# Consumer.net
KiCad netlist of a schematic drawn in Altium Designer
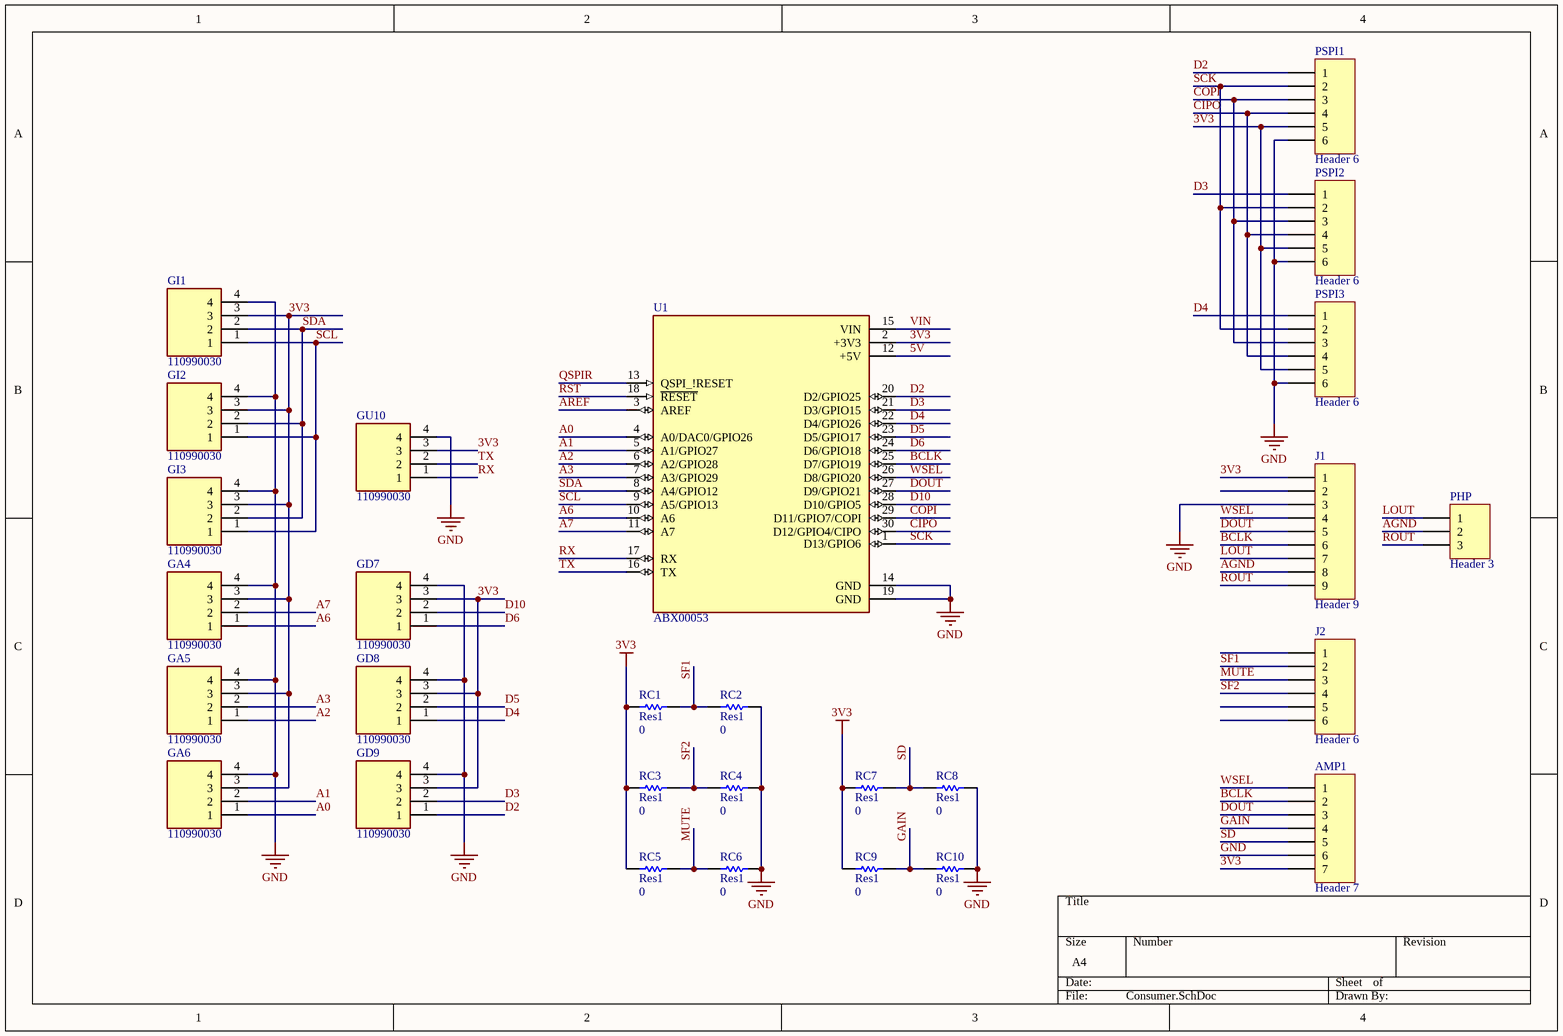
[diagram p0: Consumer.SchDoc]

(export (version "E")
  (design (tool "Eeschema 10.0.6"))
  (components
    (comp (ref "AMP1")
      (value "Header 7")
      (footprint "HDR1X7")
      (description "Header, 7-Pin")
      (fields (field (name "PUBLISHER") "Altium Limited"))
      (libsource (lib "Miscellaneous Connectors") (part "Header 7"))
    )
    (comp (ref "GA4")
      (value "110990030")
      (footprint "SEEED_110990030")
      (description "GROVE 2MM 4PIN VERT CONN 10PCS")
      (fields (field (name "MF") "Seeed Technology"))
      (libsource (lib "110990030") (part "110990030"))
    )
    (comp (ref "GA5")
      (value "110990030")
      (footprint "SEEED_110990030")
      (description "GROVE 2MM 4PIN VERT CONN 10PCS")
      (fields (field (name "MF") "Seeed Technology"))
      (libsource (lib "110990030") (part "110990030"))
    )
    (comp (ref "GA6")
      (value "110990030")
      (footprint "SEEED_110990030")
      (description "GROVE 2MM 4PIN VERT CONN 10PCS")
      (fields (field (name "MF") "Seeed Technology"))
      (libsource (lib "110990030") (part "110990030"))
    )
    (comp (ref "GD7")
      (value "110990030")
      (footprint "SEEED_110990030")
      (description "GROVE 2MM 4PIN VERT CONN 10PCS")
      (fields (field (name "MF") "Seeed Technology"))
      (libsource (lib "110990030") (part "110990030"))
    )
    (comp (ref "GD8")
      (value "110990030")
      (footprint "SEEED_110990030")
      (description "GROVE 2MM 4PIN VERT CONN 10PCS")
      (fields (field (name "MF") "Seeed Technology"))
      (libsource (lib "110990030") (part "110990030"))
    )
    (comp (ref "GD9")
      (value "110990030")
      (footprint "SEEED_110990030")
      (description "GROVE 2MM 4PIN VERT CONN 10PCS")
      (fields (field (name "MF") "Seeed Technology"))
      (libsource (lib "110990030") (part "110990030"))
    )
    (comp (ref "GI1")
      (value "110990030")
      (footprint "SEEED_110990030")
      (description "GROVE 2MM 4PIN VERT CONN 10PCS")
      (fields (field (name "MF") "Seeed Technology"))
      (libsource (lib "110990030") (part "110990030"))
    )
    (comp (ref "GI2")
      (value "110990030")
      (footprint "SEEED_110990030")
      (description "GROVE 2MM 4PIN VERT CONN 10PCS")
      (fields (field (name "MF") "Seeed Technology"))
      (libsource (lib "110990030") (part "110990030"))
    )
    (comp (ref "GI3")
      (value "110990030")
      (footprint "SEEED_110990030")
      (description "GROVE 2MM 4PIN VERT CONN 10PCS")
      (fields (field (name "MF") "Seeed Technology"))
      (libsource (lib "110990030") (part "110990030"))
    )
    (comp (ref "GU10")
      (value "110990030")
      (footprint "SEEED_110990030")
      (description "GROVE 2MM 4PIN VERT CONN 10PCS")
      (fields (field (name "MF") "Seeed Technology"))
      (libsource (lib "110990030") (part "110990030"))
    )
    (comp (ref "J1")
      (value "Header 9")
      (footprint "HDR1X9")
      (description "Header, 9-Pin")
      (fields (field (name "PUBLISHER") "Altium Limited"))
      (libsource (lib "Miscellaneous Connectors") (part "Header 9"))
    )
    (comp (ref "J2")
      (value "Header 6")
      (footprint "HDR1X6")
      (description "Header, 6-Pin")
      (fields (field (name "PUBLISHER") "Altium Limited"))
      (libsource (lib "Miscellaneous Connectors") (part "Header 6"))
    )
    (comp (ref "PHP")
      (value "Header 3")
      (footprint "HDR1X3")
      (description "Header, 3-Pin")
      (fields (field (name "PUBLISHER") "Altium Limited"))
      (libsource (lib "Miscellaneous Connectors") (part "Header 3"))
    )
    (comp (ref "PSPI1")
      (value "Header 6")
      (footprint "HDR1X6")
      (description "Header, 6-Pin")
      (fields (field (name "PUBLISHER") "Altium Limited"))
      (libsource (lib "Miscellaneous Connectors") (part "Header 6"))
    )
    (comp (ref "PSPI2")
      (value "Header 6")
      (footprint "HDR1X6")
      (description "Header, 6-Pin")
      (fields (field (name "PUBLISHER") "Altium Limited"))
      (libsource (lib "Miscellaneous Connectors") (part "Header 6"))
    )
    (comp (ref "PSPI3")
      (value "Header 6")
      (footprint "HDR1X6")
      (description "Header, 6-Pin")
      (fields (field (name "PUBLISHER") "Altium Limited"))
      (libsource (lib "Miscellaneous Connectors") (part "Header 6"))
    )
    (comp (ref "RC1")
      (value "Res1")
      (footprint "0603R-GENERIC")
      (description "Resistor")
      (fields (field (name "ALTIUM_VALUE") "0") (field (name "PUBLISHER") "Altium Limited"))
      (libsource (lib "Miscellaneous Devices") (part "Res1"))
    )
    (comp (ref "RC2")
      (value "Res1")
      (footprint "0603R-GENERIC")
      (description "Resistor")
      (fields (field (name "ALTIUM_VALUE") "0") (field (name "PUBLISHER") "Altium Limited"))
      (libsource (lib "Miscellaneous Devices") (part "Res1"))
    )
    (comp (ref "RC3")
      (value "Res1")
      (footprint "0603R-GENERIC")
      (description "Resistor")
      (fields (field (name "ALTIUM_VALUE") "0") (field (name "PUBLISHER") "Altium Limited"))
      (libsource (lib "Miscellaneous Devices") (part "Res1"))
    )
    (comp (ref "RC4")
      (value "Res1")
      (footprint "0603R-GENERIC")
      (description "Resistor")
      (fields (field (name "ALTIUM_VALUE") "0") (field (name "PUBLISHER") "Altium Limited"))
      (libsource (lib "Miscellaneous Devices") (part "Res1"))
    )
    (comp (ref "RC5")
      (value "Res1")
      (footprint "0603R-GENERIC")
      (description "Resistor")
      (fields (field (name "ALTIUM_VALUE") "0") (field (name "PUBLISHER") "Altium Limited"))
      (libsource (lib "Miscellaneous Devices") (part "Res1"))
    )
    (comp (ref "RC6")
      (value "Res1")
      (footprint "0603R-GENERIC")
      (description "Resistor")
      (fields (field (name "ALTIUM_VALUE") "0") (field (name "PUBLISHER") "Altium Limited"))
      (libsource (lib "Miscellaneous Devices") (part "Res1"))
    )
    (comp (ref "RC7")
      (value "Res1")
      (footprint "0603R-GENERIC")
      (description "Resistor")
      (fields (field (name "ALTIUM_VALUE") "0") (field (name "PUBLISHER") "Altium Limited"))
      (libsource (lib "Miscellaneous Devices") (part "Res1"))
    )
    (comp (ref "RC8")
      (value "Res1")
      (footprint "0603R-GENERIC")
      (description "Resistor")
      (fields (field (name "ALTIUM_VALUE") "0") (field (name "PUBLISHER") "Altium Limited"))
      (libsource (lib "Miscellaneous Devices") (part "Res1"))
    )
    (comp (ref "RC9")
      (value "Res1")
      (footprint "0603R-GENERIC")
      (description "Resistor")
      (fields (field (name "ALTIUM_VALUE") "0") (field (name "PUBLISHER") "Altium Limited"))
      (libsource (lib "Miscellaneous Devices") (part "Res1"))
    )
    (comp (ref "RC10")
      (value "Res1")
      (footprint "0603R-GENERIC")
      (description "Resistor")
      (fields (field (name "ALTIUM_VALUE") "0") (field (name "PUBLISHER") "Altium Limited"))
      (libsource (lib "Miscellaneous Devices") (part "Res1"))
    )
    (comp (ref "U1")
      (value "ABX00053")
      (footprint "MODULE_ABX00053")
      (description "ARDUINO NANO RP2040 CONNECT WITH")
      (fields (field (name "MF") "Arduino"))
      (libsource (lib "ABX00053") (part "ABX00053"))
    )
  )
  (nets
    (net (code "1") (name "/5V") (class "Default")
      (node (ref "U1") (pin "12") (pinfunction "+5V_12") (pintype "power_in"))
    )
    (net (code "2") (name "/A0") (class "Default")
      (node (ref "GA6") (pin "1") (pinfunction "1_1") (pintype "passive"))
      (node (ref "U1") (pin "4") (pinfunction "A0/DAC0/GPIO26_4") (pintype "bidirectional"))
    )
    (net (code "3") (name "/A1") (class "Default")
      (node (ref "GA6") (pin "2") (pinfunction "2_2") (pintype "passive"))
      (node (ref "U1") (pin "5") (pinfunction "A1/GPIO27_5") (pintype "bidirectional"))
    )
    (net (code "4") (name "/A2") (class "Default")
      (node (ref "GA5") (pin "1") (pinfunction "1_1") (pintype "passive"))
      (node (ref "U1") (pin "6") (pinfunction "A2/GPIO28_6") (pintype "bidirectional"))
    )
    (net (code "5") (name "/A3") (class "Default")
      (node (ref "GA5") (pin "2") (pinfunction "2_2") (pintype "passive"))
      (node (ref "U1") (pin "7") (pinfunction "A3/GPIO29_7") (pintype "bidirectional"))
    )
    (net (code "6") (name "/A6") (class "Default")
      (node (ref "GA4") (pin "1") (pinfunction "1_1") (pintype "passive"))
      (node (ref "U1") (pin "10") (pinfunction "A6_10") (pintype "bidirectional"))
    )
    (net (code "7") (name "/A7") (class "Default")
      (node (ref "GA4") (pin "2") (pinfunction "2_2") (pintype "passive"))
      (node (ref "U1") (pin "11") (pinfunction "A7_11") (pintype "bidirectional"))
    )
    (net (code "8") (name "/AGND") (class "Default")
      (node (ref "J1") (pin "8") (pinfunction "8_8") (pintype "passive"))
      (node (ref "PHP") (pin "2") (pinfunction "2_2") (pintype "passive"))
    )
    (net (code "9") (name "/AREF") (class "Default")
      (node (ref "U1") (pin "3") (pinfunction "AREF_3") (pintype "bidirectional"))
    )
    (net (code "10") (name "/BCLK") (class "Default")
      (node (ref "AMP1") (pin "2") (pinfunction "2_2") (pintype "passive"))
      (node (ref "J1") (pin "6") (pinfunction "6_6") (pintype "passive"))
      (node (ref "U1") (pin "25") (pinfunction "D7/GPIO19_25") (pintype "bidirectional"))
    )
    (net (code "11") (name "/CIPO") (class "Default")
      (node (ref "PSPI1") (pin "4") (pinfunction "4_4") (pintype "passive"))
      (node (ref "PSPI2") (pin "4") (pinfunction "4_4") (pintype "passive"))
      (node (ref "PSPI3") (pin "4") (pinfunction "4_4") (pintype "passive"))
      (node (ref "U1") (pin "30") (pinfunction "D12/GPIO4/CIPO_30") (pintype "bidirectional"))
    )
    (net (code "12") (name "/COPI") (class "Default")
      (node (ref "PSPI1") (pin "3") (pinfunction "3_3") (pintype "passive"))
      (node (ref "PSPI2") (pin "3") (pinfunction "3_3") (pintype "passive"))
      (node (ref "PSPI3") (pin "3") (pinfunction "3_3") (pintype "passive"))
      (node (ref "U1") (pin "29") (pinfunction "D11/GPIO7/COPI_29") (pintype "bidirectional"))
    )
    (net (code "13") (name "/D2") (class "Default")
      (node (ref "GD9") (pin "1") (pinfunction "1_1") (pintype "passive"))
      (node (ref "PSPI1") (pin "1") (pinfunction "1_1") (pintype "passive"))
      (node (ref "U1") (pin "20") (pinfunction "D2/GPIO25_20") (pintype "bidirectional"))
    )
    (net (code "14") (name "/D3") (class "Default")
      (node (ref "GD9") (pin "2") (pinfunction "2_2") (pintype "passive"))
      (node (ref "PSPI2") (pin "1") (pinfunction "1_1") (pintype "passive"))
      (node (ref "U1") (pin "21") (pinfunction "D3/GPIO15_21") (pintype "bidirectional"))
    )
    (net (code "15") (name "/D4") (class "Default")
      (node (ref "GD8") (pin "1") (pinfunction "1_1") (pintype "passive"))
      (node (ref "PSPI3") (pin "1") (pinfunction "1_1") (pintype "passive"))
      (node (ref "U1") (pin "22") (pinfunction "D4/GPIO26_22") (pintype "bidirectional"))
    )
    (net (code "16") (name "/D5") (class "Default")
      (node (ref "GD8") (pin "2") (pinfunction "2_2") (pintype "passive"))
      (node (ref "U1") (pin "23") (pinfunction "D5/GPIO17_23") (pintype "bidirectional"))
    )
    (net (code "17") (name "/D6") (class "Default")
      (node (ref "GD7") (pin "1") (pinfunction "1_1") (pintype "passive"))
      (node (ref "U1") (pin "24") (pinfunction "D6/GPIO18_24") (pintype "bidirectional"))
    )
    (net (code "18") (name "/D10") (class "Default")
      (node (ref "GD7") (pin "2") (pinfunction "2_2") (pintype "passive"))
      (node (ref "U1") (pin "28") (pinfunction "D10/GPIO5_28") (pintype "bidirectional"))
    )
    (net (code "19") (name "/DOUT") (class "Default")
      (node (ref "AMP1") (pin "3") (pinfunction "3_3") (pintype "passive"))
      (node (ref "J1") (pin "5") (pinfunction "5_5") (pintype "passive"))
      (node (ref "U1") (pin "27") (pinfunction "D9/GPIO21_27") (pintype "bidirectional"))
    )
    (net (code "20") (name "/GAIN") (class "Default")
      (node (ref "AMP1") (pin "4") (pinfunction "4_4") (pintype "passive"))
      (node (ref "RC10") (pin "1") (pinfunction "1_1") (pintype "passive"))
      (node (ref "RC9") (pin "2") (pinfunction "2_2") (pintype "passive"))
    )
    (net (code "21") (name "/LOUT") (class "Default")
      (node (ref "J1") (pin "7") (pinfunction "7_7") (pintype "passive"))
      (node (ref "PHP") (pin "1") (pinfunction "1_1") (pintype "passive"))
    )
    (net (code "22") (name "/MUTE") (class "Default")
      (node (ref "J2") (pin "3") (pinfunction "3_3") (pintype "passive"))
      (node (ref "RC5") (pin "2") (pinfunction "2_2") (pintype "passive"))
      (node (ref "RC6") (pin "1") (pinfunction "1_1") (pintype "passive"))
    )
    (net (code "23") (name "/QSPIR") (class "Default")
      (node (ref "U1") (pin "13") (pinfunction "QSPI_!RESET_13") (pintype "input"))
    )
    (net (code "24") (name "/ROUT") (class "Default")
      (node (ref "J1") (pin "9") (pinfunction "9_9") (pintype "passive"))
      (node (ref "PHP") (pin "3") (pinfunction "3_3") (pintype "passive"))
    )
    (net (code "25") (name "/RST") (class "Default")
      (node (ref "U1") (pin "18") (pinfunction "~{RESET}_18") (pintype "input"))
    )
    (net (code "26") (name "/RX") (class "Default")
      (node (ref "GU10") (pin "1") (pinfunction "1_1") (pintype "passive"))
      (node (ref "U1") (pin "17") (pinfunction "RX_17") (pintype "bidirectional"))
    )
    (net (code "27") (name "/SCK") (class "Default")
      (node (ref "PSPI1") (pin "2") (pinfunction "2_2") (pintype "passive"))
      (node (ref "PSPI2") (pin "2") (pinfunction "2_2") (pintype "passive"))
      (node (ref "PSPI3") (pin "2") (pinfunction "2_2") (pintype "passive"))
      (node (ref "U1") (pin "1") (pinfunction "D13/GPIO6_1") (pintype "bidirectional"))
    )
    (net (code "28") (name "/SCL") (class "Default")
      (node (ref "GI1") (pin "1") (pinfunction "1_1") (pintype "passive"))
      (node (ref "GI2") (pin "1") (pinfunction "1_1") (pintype "passive"))
      (node (ref "GI3") (pin "1") (pinfunction "1_1") (pintype "passive"))
      (node (ref "U1") (pin "9") (pinfunction "A5/GPIO13_9") (pintype "bidirectional"))
    )
    (net (code "29") (name "/SD") (class "Default")
      (node (ref "AMP1") (pin "5") (pinfunction "5_5") (pintype "passive"))
      (node (ref "RC7") (pin "2") (pinfunction "2_2") (pintype "passive"))
      (node (ref "RC8") (pin "1") (pinfunction "1_1") (pintype "passive"))
    )
    (net (code "30") (name "/SDA") (class "Default")
      (node (ref "GI1") (pin "2") (pinfunction "2_2") (pintype "passive"))
      (node (ref "GI2") (pin "2") (pinfunction "2_2") (pintype "passive"))
      (node (ref "GI3") (pin "2") (pinfunction "2_2") (pintype "passive"))
      (node (ref "U1") (pin "8") (pinfunction "A4/GPIO12_8") (pintype "bidirectional"))
    )
    (net (code "31") (name "/SF1") (class "Default")
      (node (ref "J2") (pin "2") (pinfunction "2_2") (pintype "passive"))
      (node (ref "RC1") (pin "2") (pinfunction "2_2") (pintype "passive"))
      (node (ref "RC2") (pin "1") (pinfunction "1_1") (pintype "passive"))
    )
    (net (code "32") (name "/SF2") (class "Default")
      (node (ref "J2") (pin "4") (pinfunction "4_4") (pintype "passive"))
      (node (ref "RC3") (pin "2") (pinfunction "2_2") (pintype "passive"))
      (node (ref "RC4") (pin "1") (pinfunction "1_1") (pintype "passive"))
    )
    (net (code "33") (name "/TX") (class "Default")
      (node (ref "GU10") (pin "2") (pinfunction "2_2") (pintype "passive"))
      (node (ref "U1") (pin "16") (pinfunction "TX_16") (pintype "bidirectional"))
    )
    (net (code "34") (name "/VIN") (class "Default")
      (node (ref "U1") (pin "15") (pinfunction "VIN_15") (pintype "power_in"))
    )
    (net (code "35") (name "/WSEL") (class "Default")
      (node (ref "AMP1") (pin "1") (pinfunction "1_1") (pintype "passive"))
      (node (ref "J1") (pin "4") (pinfunction "4_4") (pintype "passive"))
      (node (ref "U1") (pin "26") (pinfunction "D8/GPIO20_26") (pintype "bidirectional"))
    )
    (net (code "36") (name "3V3") (class "Default")
      (node (ref "AMP1") (pin "7") (pinfunction "7_7") (pintype "passive"))
      (node (ref "GA4") (pin "3") (pinfunction "3_3") (pintype "passive"))
      (node (ref "GA5") (pin "3") (pinfunction "3_3") (pintype "passive"))
      (node (ref "GA6") (pin "3") (pinfunction "3_3") (pintype "passive"))
      (node (ref "GD7") (pin "3") (pinfunction "3_3") (pintype "passive"))
      (node (ref "GD8") (pin "3") (pinfunction "3_3") (pintype "passive"))
      (node (ref "GD9") (pin "3") (pinfunction "3_3") (pintype "passive"))
      (node (ref "GI1") (pin "3") (pinfunction "3_3") (pintype "passive"))
      (node (ref "GI2") (pin "3") (pinfunction "3_3") (pintype "passive"))
      (node (ref "GI3") (pin "3") (pinfunction "3_3") (pintype "passive"))
      (node (ref "GU10") (pin "3") (pinfunction "3_3") (pintype "passive"))
      (node (ref "J1") (pin "1") (pinfunction "1_1") (pintype "passive"))
      (node (ref "PSPI1") (pin "5") (pinfunction "5_5") (pintype "passive"))
      (node (ref "PSPI2") (pin "5") (pinfunction "5_5") (pintype "passive"))
      (node (ref "PSPI3") (pin "5") (pinfunction "5_5") (pintype "passive"))
      (node (ref "RC1") (pin "1") (pinfunction "1_1") (pintype "passive"))
      (node (ref "RC3") (pin "1") (pinfunction "1_1") (pintype "passive"))
      (node (ref "RC5") (pin "1") (pinfunction "1_1") (pintype "passive"))
      (node (ref "RC7") (pin "1") (pinfunction "1_1") (pintype "passive"))
      (node (ref "RC9") (pin "1") (pinfunction "1_1") (pintype "passive"))
      (node (ref "U1") (pin "2") (pinfunction "+3V3_2") (pintype "power_in"))
    )
    (net (code "37") (name "GND") (class "Default")
      (node (ref "AMP1") (pin "6") (pinfunction "6_6") (pintype "passive"))
      (node (ref "GA4") (pin "4") (pinfunction "4_4") (pintype "passive"))
      (node (ref "GA5") (pin "4") (pinfunction "4_4") (pintype "passive"))
      (node (ref "GA6") (pin "4") (pinfunction "4_4") (pintype "passive"))
      (node (ref "GD7") (pin "4") (pinfunction "4_4") (pintype "passive"))
      (node (ref "GD8") (pin "4") (pinfunction "4_4") (pintype "passive"))
      (node (ref "GD9") (pin "4") (pinfunction "4_4") (pintype "passive"))
      (node (ref "GI1") (pin "4") (pinfunction "4_4") (pintype "passive"))
      (node (ref "GI2") (pin "4") (pinfunction "4_4") (pintype "passive"))
      (node (ref "GI3") (pin "4") (pinfunction "4_4") (pintype "passive"))
      (node (ref "GU10") (pin "4") (pinfunction "4_4") (pintype "passive"))
      (node (ref "J1") (pin "3") (pinfunction "3_3") (pintype "passive"))
      (node (ref "PSPI1") (pin "6") (pinfunction "6_6") (pintype "passive"))
      (node (ref "PSPI2") (pin "6") (pinfunction "6_6") (pintype "passive"))
      (node (ref "PSPI3") (pin "6") (pinfunction "6_6") (pintype "passive"))
      (node (ref "RC10") (pin "2") (pinfunction "2_2") (pintype "passive"))
      (node (ref "RC2") (pin "2") (pinfunction "2_2") (pintype "passive"))
      (node (ref "RC4") (pin "2") (pinfunction "2_2") (pintype "passive"))
      (node (ref "RC6") (pin "2") (pinfunction "2_2") (pintype "passive"))
      (node (ref "RC8") (pin "2") (pinfunction "2_2") (pintype "passive"))
      (node (ref "U1") (pin "14") (pinfunction "GND_14") (pintype "power_in"))
      (node (ref "U1") (pin "19") (pinfunction "GND_19") (pintype "power_in"))
    )
    (net (code "38") (name "unconnected-(J1-Pad2)") (class "Default")
      (node (ref "J1") (pin "2") (pinfunction "2_2") (pintype "passive"))
    )
    (net (code "39") (name "unconnected-(J2-Pad1)") (class "Default")
      (node (ref "J2") (pin "1") (pinfunction "1_1") (pintype "passive"))
    )
    (net (code "40") (name "unconnected-(J2-Pad5)") (class "Default")
      (node (ref "J2") (pin "5") (pinfunction "5_5") (pintype "passive"))
    )
    (net (code "41") (name "unconnected-(J2-Pad6)") (class "Default")
      (node (ref "J2") (pin "6") (pinfunction "6_6") (pintype "passive"))
    )
  )
)
